# DDR.net
KiCad netlist of a schematic drawn in Altium Designer
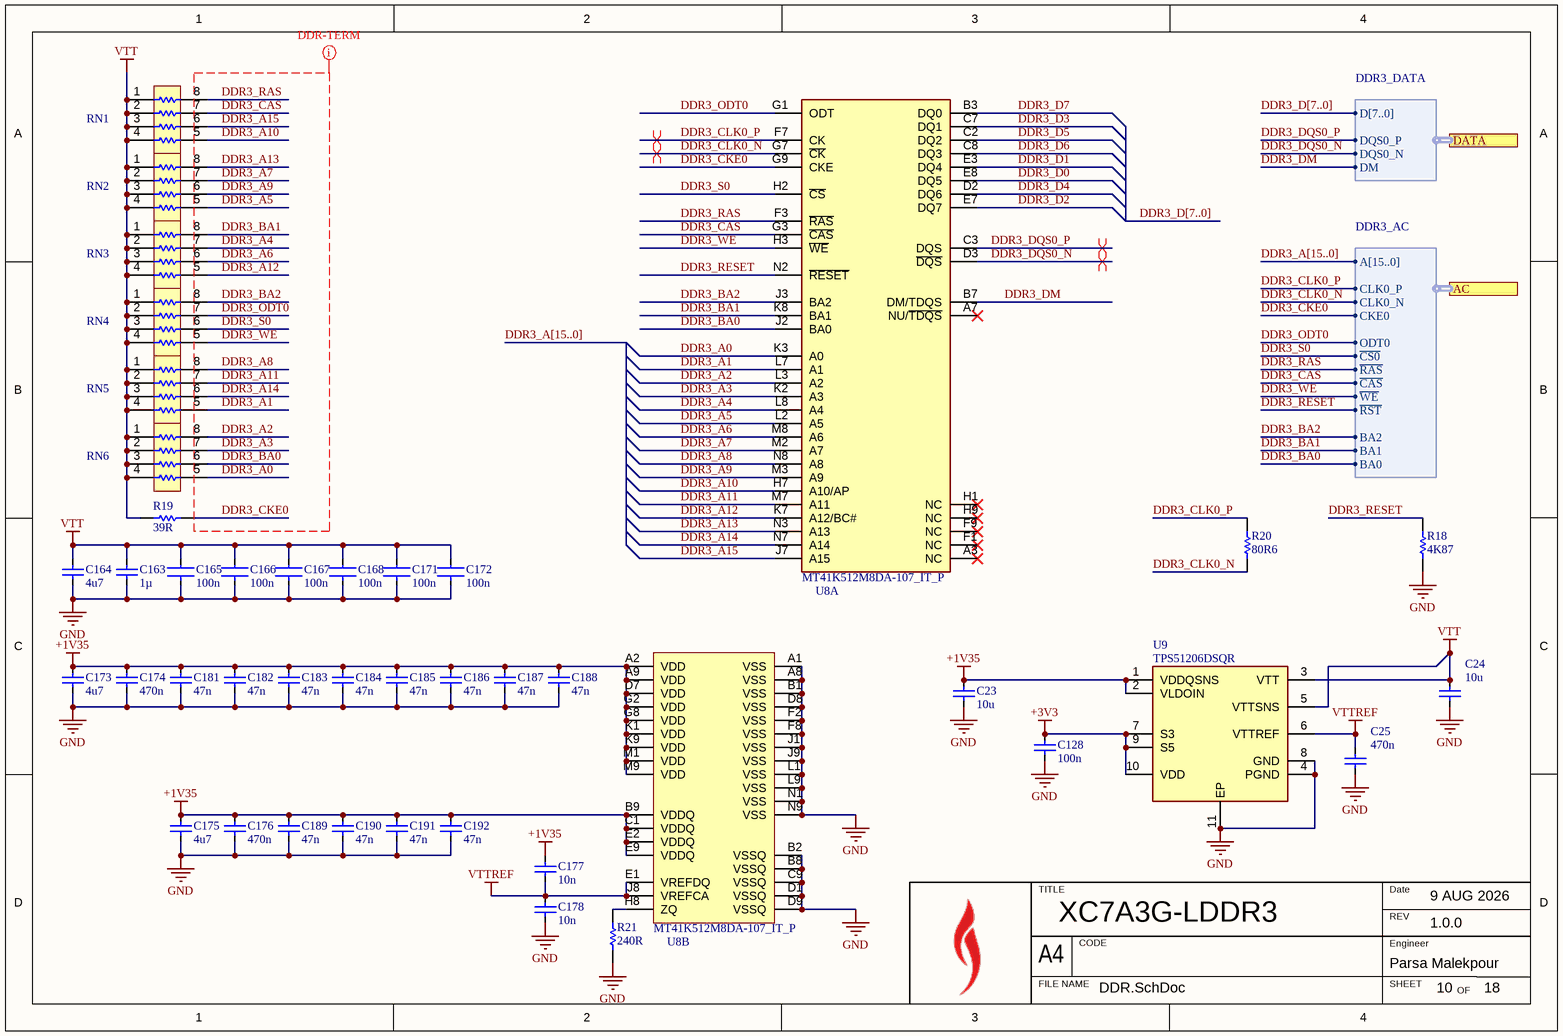
[diagram p0: DDR.SchDoc]

(export (version "E")
  (design (tool "Eeschema 10.0.6"))
  (components
    (comp (ref "C23")
      (value "10u")
      (footprint "FP-C1608-080-0_1-IPC_C")
      (description "MLCC 10μF ±10% 6.3V JB SMD 0603")
      (fields (field (name "TOLERANCE") "10%") (field (name "Comment") "C1608JB0J106K080AB"))
      (libsource (lib "Schlib1") (part "C1608JB0J106K080AB"))
    )
    (comp (ref "C24")
      (value "10u")
      (footprint "FP-C1608-080-0_1-IPC_C")
      (description "MLCC 10μF ±10% 6.3V JB SMD 0603")
      (fields (field (name "TOLERANCE") "10%") (field (name "Comment") "C1608JB0J106K080AB"))
      (libsource (lib "Schlib1") (part "C1608JB0J106K080AB"))
    )
    (comp (ref "C25")
      (value "470n")
      (footprint "pcblib1:FP-C1005-050-0_05-IPC_C")
      (description "MLCC 470nF ±10% 25V X5R SMD 0402")
      (fields (field (name "VOLTAGE") "25V") (field (name "TOLERANCE") "10%"))
      (libsource (lib "Schlib1") (part "C1005X5R1E474K050BB"))
    )
    (comp (ref "C128")
      (value "100n")
      (footprint "FP-C1005-050-0_05-IPC_C")
      (description "MLCC 100nF ±10% 50V X7R SMD 0402")
      (fields (field (name "VOLTAGE") "50V") (field (name "TOLERANCE") "10%"))
      (libsource (lib "Schlib1") (part "C1005X7R1H104K050BB"))
    )
    (comp (ref "C163")
      (value "1µ")
      (footprint "CAPC1005X55X10NL05")
      (fields
        (field (name "MANUFACTURER") "TDK")
        (field (name "TOLERANCE") "±10%")
        (field (name "PCN PART NUMBER") "MLCCPartNumberChange30/Nov/2012")
      )
      (libsource (lib "Schlib1") (part "C1005X5R1A105K050BB"))
    )
    (comp (ref "C164")
      (value "4u7")
      (footprint "PcbLib1:FP-C1005-050-0_20-0_10-IPC_C")
      (description "CAP CER 4.7UF 10V X5R 0402")
      (fields (field (name "TOLERANCE") "10%") (field (name "PART NUMBER") "C1005X5R1A475K050BE"))
      (libsource (lib "Schlib1") (part "C1005X5R1A475K050BE"))
    )
    (comp (ref "C165")
      (value "100n")
      (footprint "FP-C1005-050-0_05-IPC_C")
      (description "Multilayer Ceramic Capacitors 100nF ±10% 50V X7R SMD 0402")
      (fields (field (name "VOLTAGE") "50V") (field (name "TOLERANCE") "10%"))
      (libsource (lib "Schlib1") (part "b4654b650e69147ec39a6b967a45e02"))
    )
    (comp (ref "C166")
      (value "100n")
      (footprint "FP-C1005-050-0_05-IPC_C")
      (description "Multilayer Ceramic Capacitors 100nF ±10% 50V X7R SMD 0402")
      (fields (field (name "VOLTAGE") "50V") (field (name "TOLERANCE") "10%"))
      (libsource (lib "Schlib1") (part "b4654b650e69147ec39a6b967a45e02"))
    )
    (comp (ref "C167")
      (value "100n")
      (footprint "FP-C1005-050-0_05-IPC_C")
      (description "Multilayer Ceramic Capacitors 100nF ±10% 50V X7R SMD 0402")
      (fields (field (name "VOLTAGE") "50V") (field (name "TOLERANCE") "10%"))
      (libsource (lib "Schlib1") (part "b4654b650e69147ec39a6b967a45e02"))
    )
    (comp (ref "C168")
      (value "100n")
      (footprint "FP-C1005-050-0_05-IPC_C")
      (description "Multilayer Ceramic Capacitors 100nF ±10% 50V X7R SMD 0402")
      (fields (field (name "VOLTAGE") "50V") (field (name "TOLERANCE") "10%"))
      (libsource (lib "Schlib1") (part "b4654b650e69147ec39a6b967a45e02"))
    )
    (comp (ref "C171")
      (value "100n")
      (footprint "FP-C1005-050-0_05-IPC_C")
      (description "Multilayer Ceramic Capacitors 100nF ±10% 50V X7R SMD 0402")
      (fields (field (name "VOLTAGE") "50V") (field (name "TOLERANCE") "10%"))
      (libsource (lib "Schlib1") (part "b4654b650e69147ec39a6b967a45e02"))
    )
    (comp (ref "C172")
      (value "100n")
      (footprint "FP-C1005-050-0_05-IPC_C")
      (description "Multilayer Ceramic Capacitors 100nF ±10% 50V X7R SMD 0402")
      (fields (field (name "VOLTAGE") "50V") (field (name "TOLERANCE") "10%"))
      (libsource (lib "Schlib1") (part "b4654b650e69147ec39a6b967a45e02"))
    )
    (comp (ref "C173")
      (value "4u7")
      (footprint "PcbLib1:FP-C1005-050-0_20-0_10-IPC_C")
      (description "CAP CER 4.7UF 10V X5R 0402")
      (fields (field (name "TOLERANCE") "10%") (field (name "PART NUMBER") "C1005X5R1A475K050BE"))
      (libsource (lib "Schlib1") (part "C1005X5R1A475K050BE"))
    )
    (comp (ref "C174")
      (value "470n")
      (footprint "pcblib1:FP-C1005-050-0_05-IPC_C")
      (description "Multilayer Ceramic Capacitors 470nF ±10% 25V X5R SMD 0402")
      (fields (field (name "VOLTAGE") "25V") (field (name "TOLERANCE") "10%"))
      (libsource (lib "Schlib1") (part "C1005X5R1E474K050BB"))
    )
    (comp (ref "C175")
      (value "4u7")
      (footprint "PcbLib1:FP-C1005-050-0_20-0_10-IPC_C")
      (description "CAP CER 4.7UF 10V X5R 0402")
      (fields (field (name "TOLERANCE") "10%") (field (name "PART NUMBER") "C1005X5R1A475K050BE"))
      (libsource (lib "Schlib1") (part "C1005X5R1A475K050BE"))
    )
    (comp (ref "C176")
      (value "470n")
      (footprint "pcblib1:FP-C1005-050-0_05-IPC_C")
      (description "Multilayer Ceramic Capacitors 470nF ±10% 25V X5R SMD 0402")
      (fields (field (name "VOLTAGE") "25V") (field (name "TOLERANCE") "10%"))
      (libsource (lib "Schlib1") (part "C1005X5R1E474K050BB"))
    )
    (comp (ref "C177")
      (value "10n")
      (footprint "FP-C1005-050-0_05-IPC_C")
      (description "Multilayer Ceramic Capacitors 10nF ±10% 100V X7S SMD 0402")
      (fields (field (name "TOLERANCE") "10%") (field (name "VOLTAGE") "100V"))
      (libsource (lib "Schlib1") (part "C1005X7S2A103K050BB"))
    )
    (comp (ref "C178")
      (value "10n")
      (footprint "FP-C1005-050-0_05-IPC_C")
      (description "Multilayer Ceramic Capacitors 10nF ±10% 100V X7S SMD 0402")
      (fields (field (name "TOLERANCE") "10%") (field (name "VOLTAGE") "100V"))
      (libsource (lib "Schlib1") (part "C1005X7S2A103K050BB"))
    )
    (comp (ref "C181")
      (value "47n")
      (footprint "pcblib1:FP-C1005-050-0_05-IPC_C")
      (description "Multilayer Ceramic Capacitors 47nF ±10% 50V X7R SMD 0402")
      (fields (field (name "VOLTAGE") "50V") (field (name "TOLERANCE") "10%"))
      (libsource (lib "Schlib1") (part "C1005X7R1H473K050BB"))
    )
    (comp (ref "C182")
      (value "47n")
      (footprint "pcblib1:FP-C1005-050-0_05-IPC_C")
      (description "Multilayer Ceramic Capacitors 47nF ±10% 50V X7R SMD 0402")
      (fields (field (name "VOLTAGE") "50V") (field (name "TOLERANCE") "10%"))
      (libsource (lib "Schlib1") (part "C1005X7R1H473K050BB"))
    )
    (comp (ref "C183")
      (value "47n")
      (footprint "pcblib1:FP-C1005-050-0_05-IPC_C")
      (description "Multilayer Ceramic Capacitors 47nF ±10% 50V X7R SMD 0402")
      (fields (field (name "VOLTAGE") "50V") (field (name "TOLERANCE") "10%"))
      (libsource (lib "Schlib1") (part "C1005X7R1H473K050BB"))
    )
    (comp (ref "C184")
      (value "47n")
      (footprint "pcblib1:FP-C1005-050-0_05-IPC_C")
      (description "Multilayer Ceramic Capacitors 47nF ±10% 50V X7R SMD 0402")
      (fields (field (name "VOLTAGE") "50V") (field (name "TOLERANCE") "10%"))
      (libsource (lib "Schlib1") (part "C1005X7R1H473K050BB"))
    )
    (comp (ref "C185")
      (value "47n")
      (footprint "pcblib1:FP-C1005-050-0_05-IPC_C")
      (description "Multilayer Ceramic Capacitors 47nF ±10% 50V X7R SMD 0402")
      (fields (field (name "VOLTAGE") "50V") (field (name "TOLERANCE") "10%"))
      (libsource (lib "Schlib1") (part "C1005X7R1H473K050BB"))
    )
    (comp (ref "C186")
      (value "47n")
      (footprint "pcblib1:FP-C1005-050-0_05-IPC_C")
      (description "Multilayer Ceramic Capacitors 47nF ±10% 50V X7R SMD 0402")
      (fields (field (name "VOLTAGE") "50V") (field (name "TOLERANCE") "10%"))
      (libsource (lib "Schlib1") (part "C1005X7R1H473K050BB"))
    )
    (comp (ref "C187")
      (value "47n")
      (footprint "pcblib1:FP-C1005-050-0_05-IPC_C")
      (description "Multilayer Ceramic Capacitors 47nF ±10% 50V X7R SMD 0402")
      (fields (field (name "VOLTAGE") "50V") (field (name "TOLERANCE") "10%"))
      (libsource (lib "Schlib1") (part "C1005X7R1H473K050BB"))
    )
    (comp (ref "C188")
      (value "47n")
      (footprint "pcblib1:FP-C1005-050-0_05-IPC_C")
      (description "Multilayer Ceramic Capacitors 47nF ±10% 50V X7R SMD 0402")
      (fields (field (name "VOLTAGE") "50V") (field (name "TOLERANCE") "10%"))
      (libsource (lib "Schlib1") (part "C1005X7R1H473K050BB"))
    )
    (comp (ref "C189")
      (value "47n")
      (footprint "pcblib1:FP-C1005-050-0_05-IPC_C")
      (description "Multilayer Ceramic Capacitors 47nF ±10% 50V X7R SMD 0402")
      (fields (field (name "VOLTAGE") "50V") (field (name "TOLERANCE") "10%"))
      (libsource (lib "Schlib1") (part "C1005X7R1H473K050BB"))
    )
    (comp (ref "C190")
      (value "47n")
      (footprint "pcblib1:FP-C1005-050-0_05-IPC_C")
      (description "Multilayer Ceramic Capacitors 47nF ±10% 50V X7R SMD 0402")
      (fields (field (name "VOLTAGE") "50V") (field (name "TOLERANCE") "10%"))
      (libsource (lib "Schlib1") (part "C1005X7R1H473K050BB"))
    )
    (comp (ref "C191")
      (value "47n")
      (footprint "pcblib1:FP-C1005-050-0_05-IPC_C")
      (description "Multilayer Ceramic Capacitors 47nF ±10% 50V X7R SMD 0402")
      (fields (field (name "VOLTAGE") "50V") (field (name "TOLERANCE") "10%"))
      (libsource (lib "Schlib1") (part "C1005X7R1H473K050BB"))
    )
    (comp (ref "C192")
      (value "47n")
      (footprint "pcblib1:FP-C1005-050-0_05-IPC_C")
      (description "Multilayer Ceramic Capacitors 47nF ±10% 50V X7R SMD 0402")
      (fields (field (name "VOLTAGE") "50V") (field (name "TOLERANCE") "10%"))
      (libsource (lib "Schlib1") (part "C1005X7R1H473K050BB"))
    )
    (comp (ref "R18")
      (value "4K87")
      (footprint "RESC1005X40X25LL05T10")
      (fields (field (name "PART NUMBER") "RC0402FR-074K87L") (field (name "MANUFACTURER") "Yageo / Phycomp"))
      (libsource (lib "Schlib1") (part "RC0402FR-074K87L"))
    )
    (comp (ref "R19")
      (value "39R")
      (footprint "pcblib1:RESC1005X40X25LL05T10")
      (fields (field (name "MANUFACTURER") "Yageo / Phycomp") (field (name "PART NUMBER") "RC0402FR-0739RL"))
      (libsource (lib "Schlib1") (part "RC0402FR-0739RL"))
    )
    (comp (ref "R20")
      (value "80R6")
      (footprint "RESC1005X40X25LL05T10")
      (fields (field (name "MANUFACTURER") "Yageo") (field (name "PART NUMBER") "RC0402FR-0780R6L"))
      (libsource (lib "Schlib1") (part "RC0402FR-0780R6L"))
    )
    (comp (ref "R21")
      (value "240R")
      (footprint "pcblib1:RESC1005X40X25LL05T10")
      (description "240R 0.063W 1% 0402 (1005 Metric)  SMD")
      (fields (field (name "POWER") "0.063 W") (field (name "TOLERANCE") "1 %"))
      (libsource (lib "Schlib1") (part "RC0402FR-07240RL"))
    )
    (comp (ref "RN1")
      (value "~")
      (footprint "TC124FR0739RL")
      (description "Resistor Network")
      (fields
        (field (name "PART NUMBER") "TC124-FR-0739RL")
        (field (name "MOUSER PART NUMBER") "603-TC124-FR-0739RL")
      )
      (libsource (lib "Schlib1") (part "TC124-FR-0739RL"))
    )
    (comp (ref "RN2")
      (value "~")
      (footprint "TC124FR0739RL")
      (description "Resistor Network")
      (fields
        (field (name "PART NUMBER") "TC124-FR-0739RL")
        (field (name "MOUSER PART NUMBER") "603-TC124-FR-0739RL")
      )
      (libsource (lib "Schlib1") (part "TC124-FR-0739RL"))
    )
    (comp (ref "RN3")
      (value "~")
      (footprint "TC124FR0739RL")
      (description "Resistor Network")
      (fields
        (field (name "PART NUMBER") "TC124-FR-0739RL")
        (field (name "MOUSER PART NUMBER") "603-TC124-FR-0739RL")
      )
      (libsource (lib "Schlib1") (part "TC124-FR-0739RL"))
    )
    (comp (ref "RN4")
      (value "~")
      (footprint "TC124FR0739RL")
      (description "Resistor Network")
      (fields
        (field (name "PART NUMBER") "TC124-FR-0739RL")
        (field (name "MOUSER PART NUMBER") "603-TC124-FR-0739RL")
      )
      (libsource (lib "Schlib1") (part "TC124-FR-0739RL"))
    )
    (comp (ref "RN5")
      (value "~")
      (footprint "TC124FR0739RL")
      (description "Resistor Network")
      (fields
        (field (name "PART NUMBER") "TC124-FR-0739RL")
        (field (name "MOUSER PART NUMBER") "603-TC124-FR-0739RL")
      )
      (libsource (lib "Schlib1") (part "TC124-FR-0739RL"))
    )
    (comp (ref "RN6")
      (value "~")
      (footprint "TC124FR0739RL")
      (description "Resistor Network")
      (fields
        (field (name "PART NUMBER") "TC124-FR-0739RL")
        (field (name "MOUSER PART NUMBER") "603-TC124-FR-0739RL")
      )
      (libsource (lib "Schlib1") (part "TC124-FR-0739RL"))
    )
    (comp (ref "U8")
      (value "MT41K512M8DA-107_IT_P")
      (footprint "PCBLIB1:BGA78C80P9X13_800X1050X120")
      (description "Integrated Circuit")
      (fields
        (field (name "MANUFACTURER_PART_NUMBER") "MT41K512M8DA-107 IT:P")
        (field (name "MOUSER PART NUMBER") "340-265832-TRAY")
      )
      (libsource (lib "Schlib1") (part "MT41K512M8DA-107_IT_P"))
    )
    (comp (ref "U9")
      (value "TPS51206DSQR")
      (footprint "SON40P200X200X80-11N")
      (description "Integrated Circuit")
      (fields (field (name "MOUSER PART NUMBER") "595-TPS51206DSQR"))
      (libsource (lib "Schlib1") (part "TPS51206DSQR"))
    )
  )
  (nets
    (net (code "3") (name "+1V35") (class "Default")
      (node (ref "C173") (pin "1") (pinfunction "1_1") (pintype "passive"))
      (node (ref "C174") (pin "1") (pinfunction "1_1") (pintype "passive"))
      (node (ref "C175") (pin "1") (pinfunction "1_1") (pintype "passive"))
      (node (ref "C176") (pin "1") (pinfunction "1_1") (pintype "passive"))
      (node (ref "C177") (pin "1") (pinfunction "1_1") (pintype "passive"))
      (node (ref "C181") (pin "1") (pinfunction "1_1") (pintype "passive"))
      (node (ref "C182") (pin "1") (pinfunction "1_1") (pintype "passive"))
      (node (ref "C183") (pin "1") (pinfunction "1_1") (pintype "passive"))
      (node (ref "C184") (pin "1") (pinfunction "1_1") (pintype "passive"))
      (node (ref "C185") (pin "1") (pinfunction "1_1") (pintype "passive"))
      (node (ref "C186") (pin "1") (pinfunction "1_1") (pintype "passive"))
      (node (ref "C187") (pin "1") (pinfunction "1_1") (pintype "passive"))
      (node (ref "C188") (pin "1") (pinfunction "1_1") (pintype "passive"))
      (node (ref "C189") (pin "1") (pinfunction "1_1") (pintype "passive"))
      (node (ref "C190") (pin "1") (pinfunction "1_1") (pintype "passive"))
      (node (ref "C191") (pin "1") (pinfunction "1_1") (pintype "passive"))
      (node (ref "C192") (pin "1") (pinfunction "1_1") (pintype "passive"))
      (node (ref "C23") (pin "1") (pinfunction "1_1") (pintype "passive"))
      (node (ref "U8") (pin "A2") (pinfunction "VDD_A2") (pintype "passive"))
      (node (ref "U8") (pin "A9") (pinfunction "VDD_A9") (pintype "passive"))
      (node (ref "U8") (pin "B9") (pinfunction "VDDQ_B9") (pintype "passive"))
      (node (ref "U8") (pin "C1") (pinfunction "VDDQ_C1") (pintype "passive"))
      (node (ref "U8") (pin "D7") (pinfunction "VDD_D7") (pintype "passive"))
      (node (ref "U8") (pin "E2") (pinfunction "VDDQ_E2") (pintype "passive"))
      (node (ref "U8") (pin "E9") (pinfunction "VDDQ_E9") (pintype "passive"))
      (node (ref "U8") (pin "G2") (pinfunction "VDD_G2") (pintype "passive"))
      (node (ref "U8") (pin "G8") (pinfunction "VDD_G8") (pintype "passive"))
      (node (ref "U8") (pin "K1") (pinfunction "VDD_K1") (pintype "passive"))
      (node (ref "U8") (pin "K9") (pinfunction "VDD_K9") (pintype "passive"))
      (node (ref "U8") (pin "M1") (pinfunction "VDD_M1") (pintype "passive"))
      (node (ref "U8") (pin "M9") (pinfunction "VDD_M9") (pintype "passive"))
      (node (ref "U9") (pin "1") (pinfunction "VDDQSNS_1") (pintype "passive"))
      (node (ref "U9") (pin "2") (pinfunction "VLDOIN_2") (pintype "passive"))
    )
    (net (code "4") (name "+3V3") (class "Default")
      (node (ref "C128") (pin "1") (pinfunction "1_1") (pintype "passive"))
      (node (ref "U9") (pin "10") (pinfunction "VDD_10") (pintype "passive"))
      (node (ref "U9") (pin "7") (pinfunction "S3_7") (pintype "passive"))
      (node (ref "U9") (pin "9") (pinfunction "S5_9") (pintype "passive"))
    )
    (net (code "7") (name "/DDR3_A0") (class "Default")
      (node (ref "RN6") (pin "5") (pinfunction "5_5") (pintype "passive"))
      (node (ref "U8") (pin "K3") (pinfunction "A0_K3") (pintype "passive"))
    )
    (net (code "8") (name "/DDR3_A1") (class "Default")
      (node (ref "RN5") (pin "5") (pinfunction "5_5") (pintype "passive"))
      (node (ref "U8") (pin "L7") (pinfunction "A1_L7") (pintype "passive"))
    )
    (net (code "9") (name "/DDR3_A2") (class "Default")
      (node (ref "RN6") (pin "8") (pinfunction "8_8") (pintype "passive"))
      (node (ref "U8") (pin "L3") (pinfunction "A2_L3") (pintype "passive"))
    )
    (net (code "10") (name "/DDR3_A3") (class "Default")
      (node (ref "RN6") (pin "7") (pinfunction "7_7") (pintype "passive"))
      (node (ref "U8") (pin "K2") (pinfunction "A3_K2") (pintype "passive"))
    )
    (net (code "11") (name "/DDR3_A4") (class "Default")
      (node (ref "RN3") (pin "7") (pinfunction "7_7") (pintype "passive"))
      (node (ref "U8") (pin "L8") (pinfunction "A4_L8") (pintype "passive"))
    )
    (net (code "12") (name "/DDR3_A5") (class "Default")
      (node (ref "RN2") (pin "5") (pinfunction "5_5") (pintype "passive"))
      (node (ref "U8") (pin "L2") (pinfunction "A5_L2") (pintype "passive"))
    )
    (net (code "13") (name "/DDR3_A6") (class "Default")
      (node (ref "RN3") (pin "6") (pinfunction "6_6") (pintype "passive"))
      (node (ref "U8") (pin "M8") (pinfunction "A6_M8") (pintype "passive"))
    )
    (net (code "14") (name "/DDR3_A7") (class "Default")
      (node (ref "RN2") (pin "7") (pinfunction "7_7") (pintype "passive"))
      (node (ref "U8") (pin "M2") (pinfunction "A7_M2") (pintype "passive"))
    )
    (net (code "15") (name "/DDR3_A8") (class "Default")
      (node (ref "RN5") (pin "8") (pinfunction "8_8") (pintype "passive"))
      (node (ref "U8") (pin "N8") (pinfunction "A8_N8") (pintype "passive"))
    )
    (net (code "16") (name "/DDR3_A9") (class "Default")
      (node (ref "RN2") (pin "6") (pinfunction "6_6") (pintype "passive"))
      (node (ref "U8") (pin "M3") (pinfunction "A9_M3") (pintype "passive"))
    )
    (net (code "17") (name "/DDR3_A10") (class "Default")
      (node (ref "RN1") (pin "5") (pinfunction "5_5") (pintype "passive"))
      (node (ref "U8") (pin "H7") (pinfunction "A10/AP_H7") (pintype "passive"))
    )
    (net (code "18") (name "/DDR3_A11") (class "Default")
      (node (ref "RN5") (pin "7") (pinfunction "7_7") (pintype "passive"))
      (node (ref "U8") (pin "M7") (pinfunction "A11_M7") (pintype "passive"))
    )
    (net (code "19") (name "/DDR3_A12") (class "Default")
      (node (ref "RN3") (pin "5") (pinfunction "5_5") (pintype "passive"))
      (node (ref "U8") (pin "K7") (pinfunction "A12/BC#_K7") (pintype "passive"))
    )
    (net (code "20") (name "/DDR3_A13") (class "Default")
      (node (ref "RN2") (pin "8") (pinfunction "8_8") (pintype "passive"))
      (node (ref "U8") (pin "N3") (pinfunction "A13_N3") (pintype "passive"))
    )
    (net (code "21") (name "/DDR3_A14") (class "Default")
      (node (ref "RN5") (pin "6") (pinfunction "6_6") (pintype "passive"))
      (node (ref "U8") (pin "N7") (pinfunction "A14_N7") (pintype "passive"))
    )
    (net (code "22") (name "/DDR3_A15") (class "Default")
      (node (ref "RN1") (pin "6") (pinfunction "6_6") (pintype "passive"))
      (node (ref "U8") (pin "J7") (pinfunction "A15_J7") (pintype "passive"))
    )
    (net (code "24") (name "/DDR3_BA0") (class "Default")
      (node (ref "RN6") (pin "6") (pinfunction "6_6") (pintype "passive"))
      (node (ref "U8") (pin "J2") (pinfunction "BA0_J2") (pintype "passive"))
    )
    (net (code "25") (name "/DDR3_BA1") (class "Default")
      (node (ref "RN3") (pin "8") (pinfunction "8_8") (pintype "passive"))
      (node (ref "U8") (pin "K8") (pinfunction "BA1_K8") (pintype "passive"))
    )
    (net (code "26") (name "/DDR3_BA2") (class "Default")
      (node (ref "RN4") (pin "8") (pinfunction "8_8") (pintype "passive"))
      (node (ref "U8") (pin "J3") (pinfunction "BA2_J3") (pintype "passive"))
    )
    (net (code "27") (name "/DDR3_CAS") (class "Default")
      (node (ref "RN1") (pin "7") (pinfunction "7_7") (pintype "passive"))
      (node (ref "U8") (pin "G3") (pinfunction "~{CAS}_G3") (pintype "passive"))
    )
    (net (code "28") (name "/DDR3_CKE0") (class "Default")
      (node (ref "R19") (pin "2") (pinfunction "2_2") (pintype "passive"))
      (node (ref "U8") (pin "G9") (pinfunction "CKE_G9") (pintype "passive"))
    )
    (net (code "29") (name "/DDR3_CLK0_N") (class "Default")
      (node (ref "R20") (pin "2") (pinfunction "2_2") (pintype "passive"))
      (node (ref "U8") (pin "G7") (pinfunction "~{CK}_G7") (pintype "passive"))
    )
    (net (code "30") (name "/DDR3_CLK0_P") (class "Default")
      (node (ref "R20") (pin "1") (pinfunction "1_1") (pintype "passive"))
      (node (ref "U8") (pin "F7") (pinfunction "CK_F7") (pintype "passive"))
    )
    (net (code "31") (name "/DDR3_D0") (class "Default")
      (node (ref "U8") (pin "E8") (pinfunction "DQ5_E8") (pintype "passive"))
    )
    (net (code "32") (name "/DDR3_D1") (class "Default")
      (node (ref "U8") (pin "E3") (pinfunction "DQ4_E3") (pintype "passive"))
    )
    (net (code "33") (name "/DDR3_D2") (class "Default")
      (node (ref "U8") (pin "E7") (pinfunction "DQ7_E7") (pintype "passive"))
    )
    (net (code "34") (name "/DDR3_D3") (class "Default")
      (node (ref "U8") (pin "C7") (pinfunction "DQ1_C7") (pintype "passive"))
    )
    (net (code "35") (name "/DDR3_D4") (class "Default")
      (node (ref "U8") (pin "D2") (pinfunction "DQ6_D2") (pintype "passive"))
    )
    (net (code "36") (name "/DDR3_D5") (class "Default")
      (node (ref "U8") (pin "C2") (pinfunction "DQ2_C2") (pintype "passive"))
    )
    (net (code "37") (name "/DDR3_D6") (class "Default")
      (node (ref "U8") (pin "C8") (pinfunction "DQ3_C8") (pintype "passive"))
    )
    (net (code "38") (name "/DDR3_D7") (class "Default")
      (node (ref "U8") (pin "B3") (pinfunction "DQ0_B3") (pintype "passive"))
    )
    (net (code "39") (name "/DDR3_DM") (class "Default")
      (node (ref "U8") (pin "B7") (pinfunction "DM/TDQS_B7") (pintype "passive"))
    )
    (net (code "40") (name "/DDR3_DQS0_N") (class "Default")
      (node (ref "U8") (pin "D3") (pinfunction "~{DQS}_D3") (pintype "passive"))
    )
    (net (code "41") (name "/DDR3_DQS0_P") (class "Default")
      (node (ref "U8") (pin "C3") (pinfunction "DQS_C3") (pintype "passive"))
    )
    (net (code "43") (name "/DDR3_ODT0") (class "Default")
      (node (ref "RN4") (pin "7") (pinfunction "7_7") (pintype "passive"))
      (node (ref "U8") (pin "G1") (pinfunction "ODT_G1") (pintype "passive"))
    )
    (net (code "44") (name "/DDR3_RAS") (class "Default")
      (node (ref "RN1") (pin "8") (pinfunction "8_8") (pintype "passive"))
      (node (ref "U8") (pin "F3") (pinfunction "~{RAS}_F3") (pintype "passive"))
    )
    (net (code "45") (name "/DDR3_RESET") (class "Default")
      (node (ref "R18") (pin "2") (pinfunction "2_2") (pintype "passive"))
      (node (ref "U8") (pin "N2") (pinfunction "~{RESET}_N2") (pintype "passive"))
    )
    (net (code "46") (name "/DDR3_S0") (class "Default")
      (node (ref "RN4") (pin "6") (pinfunction "6_6") (pintype "passive"))
      (node (ref "U8") (pin "H2") (pinfunction "~{CS}_H2") (pintype "passive"))
    )
    (net (code "47") (name "/DDR3_WE") (class "Default")
      (node (ref "RN4") (pin "5") (pinfunction "5_5") (pintype "passive"))
      (node (ref "U8") (pin "H3") (pinfunction "~{WE}_H3") (pintype "passive"))
    )
    (net (code "50") (name "GND") (class "Default")
      (node (ref "C128") (pin "2") (pinfunction "2_2") (pintype "passive"))
      (node (ref "C163") (pin "2") (pinfunction "2_2") (pintype "passive"))
      (node (ref "C164") (pin "2") (pinfunction "2_2") (pintype "passive"))
      (node (ref "C165") (pin "1") (pinfunction "1_1") (pintype "passive"))
      (node (ref "C166") (pin "1") (pinfunction "1_1") (pintype "passive"))
      (node (ref "C167") (pin "1") (pinfunction "1_1") (pintype "passive"))
      (node (ref "C168") (pin "1") (pinfunction "1_1") (pintype "passive"))
      (node (ref "C171") (pin "1") (pinfunction "1_1") (pintype "passive"))
      (node (ref "C172") (pin "1") (pinfunction "1_1") (pintype "passive"))
      (node (ref "C173") (pin "2") (pinfunction "2_2") (pintype "passive"))
      (node (ref "C174") (pin "2") (pinfunction "2_2") (pintype "passive"))
      (node (ref "C175") (pin "2") (pinfunction "2_2") (pintype "passive"))
      (node (ref "C176") (pin "2") (pinfunction "2_2") (pintype "passive"))
      (node (ref "C178") (pin "2") (pinfunction "2_2") (pintype "passive"))
      (node (ref "C181") (pin "2") (pinfunction "2_2") (pintype "passive"))
      (node (ref "C182") (pin "2") (pinfunction "2_2") (pintype "passive"))
      (node (ref "C183") (pin "2") (pinfunction "2_2") (pintype "passive"))
      (node (ref "C184") (pin "2") (pinfunction "2_2") (pintype "passive"))
      (node (ref "C185") (pin "2") (pinfunction "2_2") (pintype "passive"))
      (node (ref "C186") (pin "2") (pinfunction "2_2") (pintype "passive"))
      (node (ref "C187") (pin "2") (pinfunction "2_2") (pintype "passive"))
      (node (ref "C188") (pin "2") (pinfunction "2_2") (pintype "passive"))
      (node (ref "C189") (pin "2") (pinfunction "2_2") (pintype "passive"))
      (node (ref "C190") (pin "2") (pinfunction "2_2") (pintype "passive"))
      (node (ref "C191") (pin "2") (pinfunction "2_2") (pintype "passive"))
      (node (ref "C192") (pin "2") (pinfunction "2_2") (pintype "passive"))
      (node (ref "C23") (pin "2") (pinfunction "2_2") (pintype "passive"))
      (node (ref "C24") (pin "1") (pinfunction "1_1") (pintype "passive"))
      (node (ref "C25") (pin "1") (pinfunction "1_1") (pintype "passive"))
      (node (ref "R18") (pin "1") (pinfunction "1_1") (pintype "passive"))
      (node (ref "R21") (pin "2") (pinfunction "2_2") (pintype "passive"))
      (node (ref "U8") (pin "A1") (pinfunction "VSS_A1") (pintype "passive"))
      (node (ref "U8") (pin "A8") (pinfunction "VSS_A8") (pintype "passive"))
      (node (ref "U8") (pin "B1") (pinfunction "VSS_B1") (pintype "passive"))
      (node (ref "U8") (pin "B2") (pinfunction "VSSQ_B2") (pintype "passive"))
      (node (ref "U8") (pin "B8") (pinfunction "VSSQ_B8") (pintype "passive"))
      (node (ref "U8") (pin "C9") (pinfunction "VSSQ_C9") (pintype "passive"))
      (node (ref "U8") (pin "D1") (pinfunction "VSSQ_D1") (pintype "passive"))
      (node (ref "U8") (pin "D8") (pinfunction "VSS_D8") (pintype "passive"))
      (node (ref "U8") (pin "D9") (pinfunction "VSSQ_D9") (pintype "passive"))
      (node (ref "U8") (pin "F2") (pinfunction "VSS_F2") (pintype "passive"))
      (node (ref "U8") (pin "F8") (pinfunction "VSS_F8") (pintype "passive"))
      (node (ref "U8") (pin "J1") (pinfunction "VSS_J1") (pintype "passive"))
      (node (ref "U8") (pin "J9") (pinfunction "VSS_J9") (pintype "passive"))
      (node (ref "U8") (pin "L1") (pinfunction "VSS_L1") (pintype "passive"))
      (node (ref "U8") (pin "L9") (pinfunction "VSS_L9") (pintype "passive"))
      (node (ref "U8") (pin "N1") (pinfunction "VSS_N1") (pintype "passive"))
      (node (ref "U8") (pin "N9") (pinfunction "VSS_N9") (pintype "passive"))
      (node (ref "U9") (pin "11") (pinfunction "EP_11") (pintype "passive"))
      (node (ref "U9") (pin "4") (pinfunction "PGND_4") (pintype "passive"))
      (node (ref "U9") (pin "8") (pinfunction "GND_8") (pintype "passive"))
    )
    (net (code "51") (name "Net-(U8B-ZQ)") (class "Default")
      (node (ref "R21") (pin "1") (pinfunction "1_1") (pintype "passive"))
      (node (ref "U8") (pin "H8") (pinfunction "ZQ_H8") (pintype "passive"))
    )
    (net (code "52") (name "VTT") (class "Default")
      (node (ref "C163") (pin "1") (pinfunction "1_1") (pintype "passive"))
      (node (ref "C164") (pin "1") (pinfunction "1_1") (pintype "passive"))
      (node (ref "C165") (pin "2") (pinfunction "2_2") (pintype "passive"))
      (node (ref "C166") (pin "2") (pinfunction "2_2") (pintype "passive"))
      (node (ref "C167") (pin "2") (pinfunction "2_2") (pintype "passive"))
      (node (ref "C168") (pin "2") (pinfunction "2_2") (pintype "passive"))
      (node (ref "C171") (pin "2") (pinfunction "2_2") (pintype "passive"))
      (node (ref "C172") (pin "2") (pinfunction "2_2") (pintype "passive"))
      (node (ref "C24") (pin "2") (pinfunction "2_2") (pintype "passive"))
      (node (ref "R19") (pin "1") (pinfunction "1_1") (pintype "passive"))
      (node (ref "RN1") (pin "1") (pinfunction "1_1") (pintype "passive"))
      (node (ref "RN1") (pin "2") (pinfunction "2_2") (pintype "passive"))
      (node (ref "RN1") (pin "3") (pinfunction "3_3") (pintype "passive"))
      (node (ref "RN1") (pin "4") (pinfunction "4_4") (pintype "passive"))
      (node (ref "RN2") (pin "1") (pinfunction "1_1") (pintype "passive"))
      (node (ref "RN2") (pin "2") (pinfunction "2_2") (pintype "passive"))
      (node (ref "RN2") (pin "3") (pinfunction "3_3") (pintype "passive"))
      (node (ref "RN2") (pin "4") (pinfunction "4_4") (pintype "passive"))
      (node (ref "RN3") (pin "1") (pinfunction "1_1") (pintype "passive"))
      (node (ref "RN3") (pin "2") (pinfunction "2_2") (pintype "passive"))
      (node (ref "RN3") (pin "3") (pinfunction "3_3") (pintype "passive"))
      (node (ref "RN3") (pin "4") (pinfunction "4_4") (pintype "passive"))
      (node (ref "RN4") (pin "1") (pinfunction "1_1") (pintype "passive"))
      (node (ref "RN4") (pin "2") (pinfunction "2_2") (pintype "passive"))
      (node (ref "RN4") (pin "3") (pinfunction "3_3") (pintype "passive"))
      (node (ref "RN4") (pin "4") (pinfunction "4_4") (pintype "passive"))
      (node (ref "RN5") (pin "1") (pinfunction "1_1") (pintype "passive"))
      (node (ref "RN5") (pin "2") (pinfunction "2_2") (pintype "passive"))
      (node (ref "RN5") (pin "3") (pinfunction "3_3") (pintype "passive"))
      (node (ref "RN5") (pin "4") (pinfunction "4_4") (pintype "passive"))
      (node (ref "RN6") (pin "1") (pinfunction "1_1") (pintype "passive"))
      (node (ref "RN6") (pin "2") (pinfunction "2_2") (pintype "passive"))
      (node (ref "RN6") (pin "3") (pinfunction "3_3") (pintype "passive"))
      (node (ref "RN6") (pin "4") (pinfunction "4_4") (pintype "passive"))
      (node (ref "U9") (pin "3") (pinfunction "VTT_3") (pintype "passive"))
      (node (ref "U9") (pin "5") (pinfunction "VTTSNS_5") (pintype "passive"))
    )
    (net (code "53") (name "VTTREF") (class "Default")
      (node (ref "C177") (pin "2") (pinfunction "2_2") (pintype "passive"))
      (node (ref "C178") (pin "1") (pinfunction "1_1") (pintype "passive"))
      (node (ref "C25") (pin "2") (pinfunction "2_2") (pintype "passive"))
      (node (ref "U8") (pin "E1") (pinfunction "VREFDQ_E1") (pintype "passive"))
      (node (ref "U8") (pin "J8") (pinfunction "VREFCA_J8") (pintype "passive"))
      (node (ref "U9") (pin "6") (pinfunction "VTTREF_6") (pintype "passive"))
    )
    (net (code "54") (name "unconnected-(U8A-NC-PadA3)") (class "Default")
      (node (ref "U8") (pin "A3") (pinfunction "NC_A3") (pintype "passive+no_connect"))
    )
    (net (code "55") (name "unconnected-(U8A-NC-PadF1)") (class "Default")
      (node (ref "U8") (pin "F1") (pinfunction "NC_F1") (pintype "passive+no_connect"))
    )
    (net (code "56") (name "unconnected-(U8A-NC-PadF9)") (class "Default")
      (node (ref "U8") (pin "F9") (pinfunction "NC_F9") (pintype "passive+no_connect"))
    )
    (net (code "57") (name "unconnected-(U8A-NC-PadH1)") (class "Default")
      (node (ref "U8") (pin "H1") (pinfunction "NC_H1") (pintype "passive+no_connect"))
    )
    (net (code "58") (name "unconnected-(U8A-NC-PadH9)") (class "Default")
      (node (ref "U8") (pin "H9") (pinfunction "NC_H9") (pintype "passive+no_connect"))
    )
    (net (code "59") (name "unconnected-(U8A-NU{slash}~{TDQS}-PadA7)") (class "Default")
      (node (ref "U8") (pin "A7") (pinfunction "NU/~{TDQS}_A7") (pintype "passive+no_connect"))
    )
  )
)
